# programmer.net
KiCad netlist of a schematic drawn in EAGLE
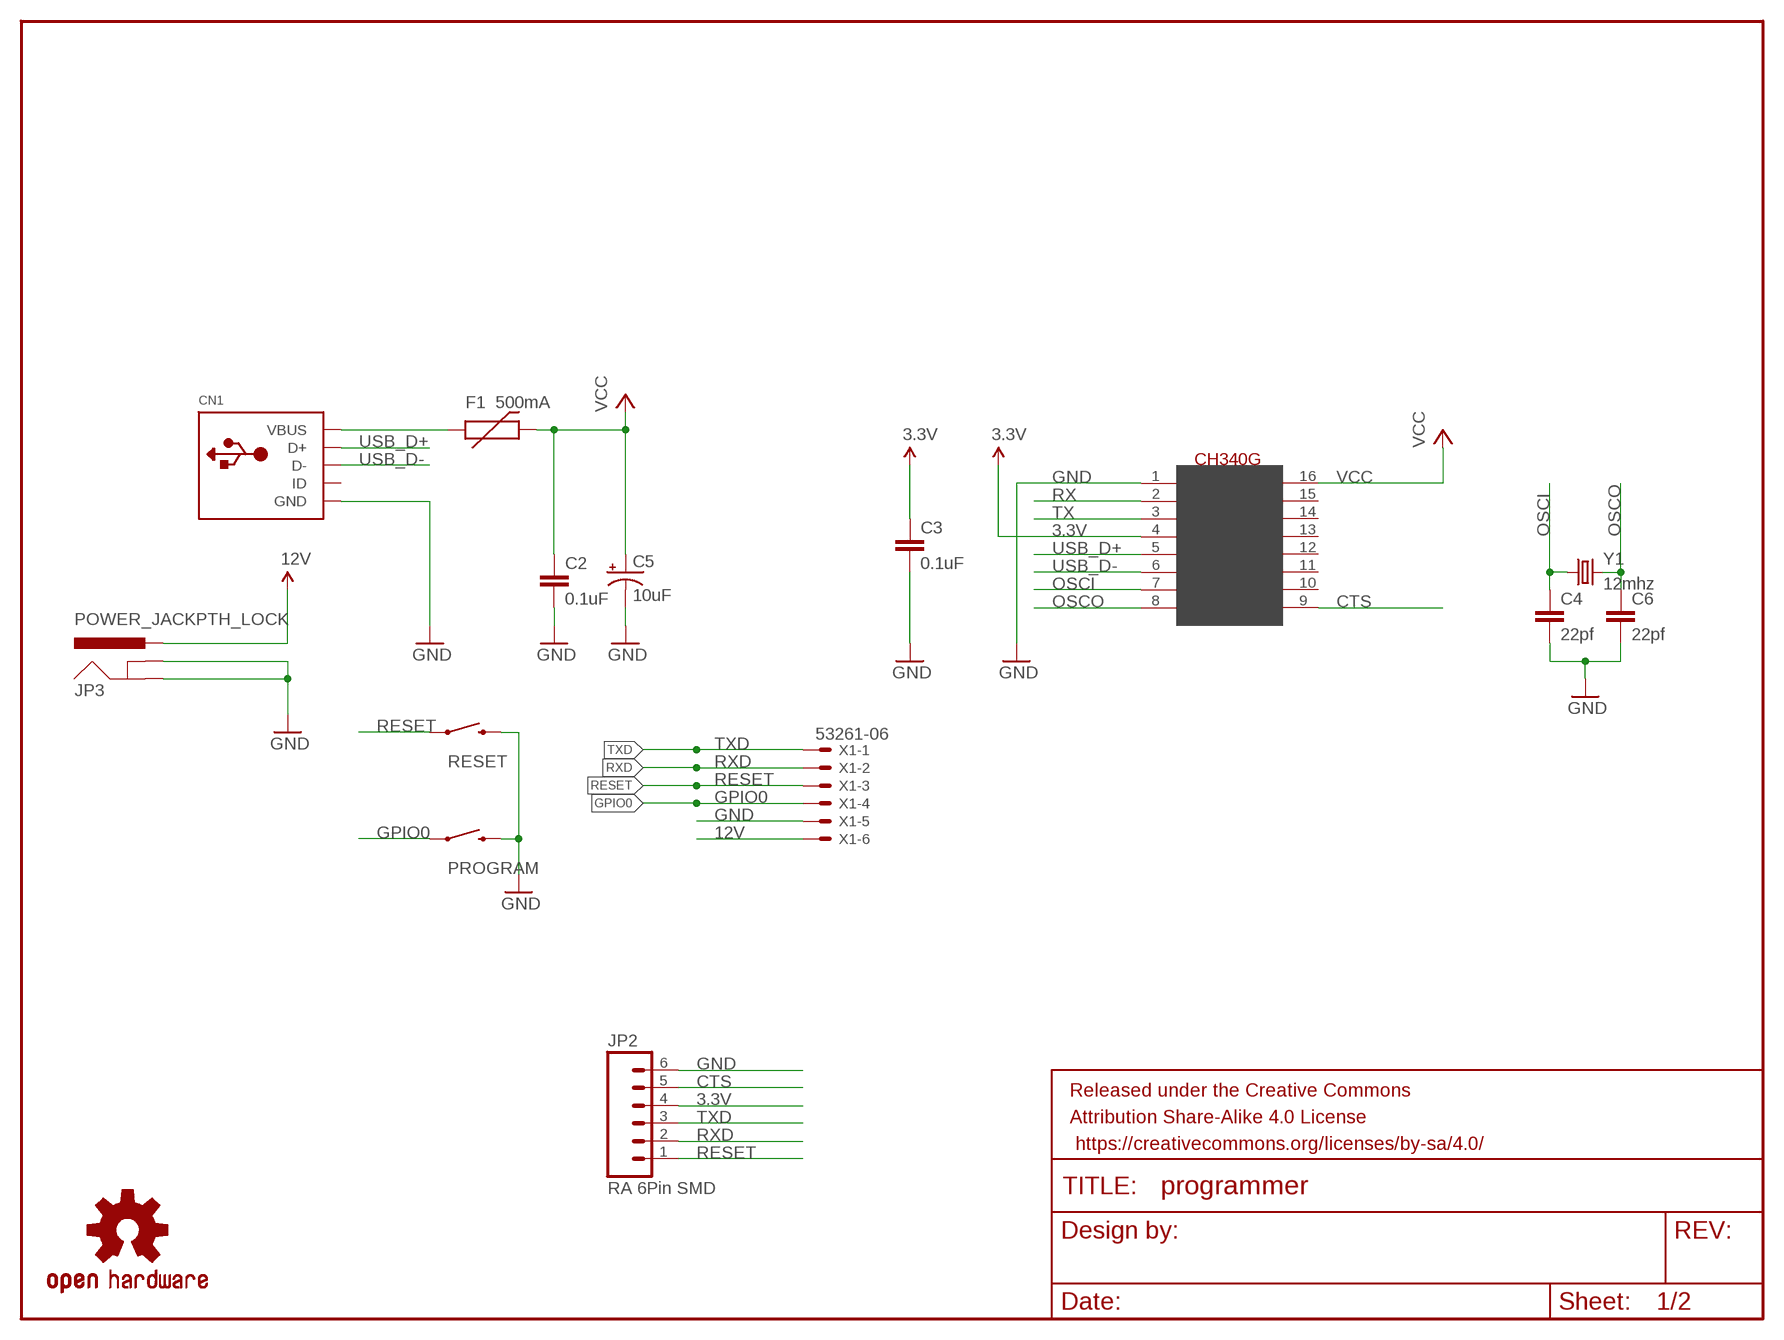
[diagram p0: schematic, sheet 1]

(export (version "E")
  (design (tool "Eeschema 10.0.6"))
  (components
    (comp (ref "C2")
      (value "0.1uF")
      (footprint "eagle-import:1206")
      (libsource (lib "eagle-import") (part "SparkFun-Passives_CAP1206"))
    )
    (comp (ref "C3")
      (value "0.1uF")
      (footprint "eagle-import:C1206K")
      (libsource (lib "eagle-import") (part "C-EUC1206K"))
    )
    (comp (ref "C4")
      (value "22pf")
      (footprint "eagle-import:1206")
      (libsource (lib "eagle-import") (part "CAP1206"))
    )
    (comp (ref "C5")
      (value "10uF")
      (footprint "eagle-import:EIA3216")
      (libsource (lib "eagle-import") (part "10UF-16V-10%(TANT)"))
    )
    (comp (ref "C6")
      (value "22pf")
      (footprint "eagle-import:1206")
      (libsource (lib "eagle-import") (part "CAP1206"))
    )
    (comp (ref "CN1")
      (value "USBMINIB")
      (footprint "eagle-import:USB-MINIB")
      (libsource (lib "eagle-import") (part "USBMINIB"))
    )
    (comp (ref "F1")
      (value "500mA")
      (footprint "eagle-import:PTC-1206")
      (libsource (lib "eagle-import") (part "PTCSMD"))
    )
    (comp (ref "FRAME1")
      (value "FRAME-LETTERNO_PACKAGE")
      (footprint "eagle-import:DUMMY")
      (fields (field (name "DESIGNER") "Nobody"))
      (libsource (lib "eagle-import") (part "FRAME-LETTERNO_PACKAGE"))
    )
    (comp (ref "JP2")
      (value "RA 6Pin SMD")
      (footprint "eagle-import:1X06-SMD")
      (libsource (lib "eagle-import") (part "M06SMD"))
    )
    (comp (ref "JP3")
      (value "POWER_JACKPTH_LOCK")
      (footprint "eagle-import:POWER_JACK_PTH_LOCK")
      (libsource (lib "eagle-import") (part "POWER_JACKPTH_LOCK"))
    )
    (comp (ref "LOGO1")
      (value "OSHW-LOGOS")
      (footprint "eagle-import:OSHW-LOGO-S")
      (libsource (lib "eagle-import") (part "OSHW-LOGOS"))
    )
    (comp (ref "PROGRAM")
      (value "SWITCH-MOMENTARY-2PTH")
      (footprint "eagle-import:TACTILE-PTH")
      (libsource (lib "eagle-import") (part "SWITCH-MOMENTARY-2PTH"))
    )
    (comp (ref "RESET")
      (value "SWITCH-MOMENTARY-2PTH")
      (footprint "eagle-import:TACTILE-PTH")
      (libsource (lib "eagle-import") (part "SWITCH-MOMENTARY-2PTH"))
    )
    (comp (ref "U$1")
      (value "CH340G")
      (footprint "eagle-import:SOIC16")
      (libsource (lib "eagle-import") (part "CH340G"))
    )
    (comp (ref "X1")
      (value "53261-06")
      (footprint "eagle-import:53261-06")
      (libsource (lib "eagle-import") (part "53?-06261"))
    )
    (comp (ref "Y1")
      (value "12mhz")
      (footprint "eagle-import:HC49UP")
      (libsource (lib "eagle-import") (part "CRYSTALSMD"))
    )
  )
  (nets
    (net (code "1") (name "3.3V") (class "Default")
      (node (ref "C3") (pin "1") (pinfunction "1_1") (pintype "passive"))
      (node (ref "JP2") (pin "4") (pinfunction "4_4") (pintype "passive"))
      (node (ref "U$1") (pin "4") (pinfunction "V3_4") (pintype "bidirectional"))
    )
    (net (code "2") (name "12V") (class "Default")
      (node (ref "JP3") (pin "PWR") (pinfunction "PWR_PWR") (pintype "bidirectional"))
      (node (ref "X1") (pin "6") (pinfunction "S_6") (pintype "passive"))
    )
    (net (code "3") (name "CTS") (class "Default")
      (node (ref "JP2") (pin "5") (pinfunction "5_5") (pintype "passive"))
      (node (ref "U$1") (pin "9") (pinfunction "CTS_9") (pintype "bidirectional"))
    )
    (net (code "4") (name "GND") (class "Default")
      (node (ref "C2") (pin "2") (pinfunction "2_2") (pintype "passive"))
      (node (ref "C3") (pin "2") (pinfunction "2_2") (pintype "passive"))
      (node (ref "C4") (pin "2") (pinfunction "2_2") (pintype "passive"))
      (node (ref "C5") (pin "C") (pinfunction "-_C") (pintype "passive"))
      (node (ref "C6") (pin "2") (pinfunction "2_2") (pintype "passive"))
      (node (ref "CN1") (pin "GND") (pinfunction "GND_GND") (pintype "power_in"))
      (node (ref "JP2") (pin "6") (pinfunction "6_6") (pintype "passive"))
      (node (ref "JP3") (pin "GND") (pinfunction "GND_GND") (pintype "bidirectional"))
      (node (ref "JP3") (pin "GNDBREAK") (pinfunction "GNDBREAK_GNDBREAK") (pintype "bidirectional"))
      (node (ref "PROGRAM") (pin "3") (pinfunction "2_3") (pintype "passive"))
      (node (ref "RESET") (pin "3") (pinfunction "2_3") (pintype "passive"))
      (node (ref "U$1") (pin "1") (pinfunction "GND_1") (pintype "bidirectional"))
      (node (ref "X1") (pin "5") (pinfunction "S_5") (pintype "passive"))
    )
    (net (code "5") (name "GPIO0") (class "Default")
      (node (ref "PROGRAM") (pin "1") (pinfunction "1_1") (pintype "passive"))
      (node (ref "X1") (pin "4") (pinfunction "S_4") (pintype "passive"))
    )
    (net (code "6") (name "Net-(CN1-PadVBUS)") (class "Default")
      (node (ref "CN1") (pin "VBUS") (pinfunction "VBUS_VBUS") (pintype "power_in"))
      (node (ref "F1") (pin "1") (pinfunction "1_1") (pintype "bidirectional"))
    )
    (net (code "7") (name "OSCI") (class "Default")
      (node (ref "C4") (pin "1") (pinfunction "1_1") (pintype "passive"))
      (node (ref "U$1") (pin "7") (pinfunction "XI_7") (pintype "bidirectional"))
      (node (ref "Y1") (pin "1") (pinfunction "1_1") (pintype "passive"))
    )
    (net (code "8") (name "OSCO") (class "Default")
      (node (ref "C6") (pin "1") (pinfunction "1_1") (pintype "passive"))
      (node (ref "U$1") (pin "8") (pinfunction "XO_8") (pintype "bidirectional"))
      (node (ref "Y1") (pin "2") (pinfunction "2_2") (pintype "passive"))
    )
    (net (code "9") (name "RESET") (class "Default")
      (node (ref "JP2") (pin "1") (pinfunction "1_1") (pintype "passive"))
      (node (ref "RESET") (pin "1") (pinfunction "1_1") (pintype "passive"))
      (node (ref "X1") (pin "3") (pinfunction "S_3") (pintype "passive"))
    )
    (net (code "10") (name "RX") (class "Default")
      (node (ref "U$1") (pin "2") (pinfunction "TX_2") (pintype "bidirectional"))
    )
    (net (code "11") (name "RXD") (class "Default")
      (node (ref "JP2") (pin "2") (pinfunction "2_2") (pintype "passive"))
      (node (ref "X1") (pin "2") (pinfunction "S_2") (pintype "passive"))
    )
    (net (code "12") (name "TX") (class "Default")
      (node (ref "U$1") (pin "3") (pinfunction "RX_3") (pintype "bidirectional"))
    )
    (net (code "13") (name "TXD") (class "Default")
      (node (ref "JP2") (pin "3") (pinfunction "3_3") (pintype "passive"))
      (node (ref "X1") (pin "1") (pinfunction "S_1") (pintype "passive"))
    )
    (net (code "14") (name "USB_D+") (class "Default")
      (node (ref "CN1") (pin "D+") (pinfunction "D+_D+") (pintype "bidirectional"))
      (node (ref "U$1") (pin "5") (pinfunction "D+_5") (pintype "bidirectional"))
    )
    (net (code "15") (name "USB_D-") (class "Default")
      (node (ref "CN1") (pin "D-") (pinfunction "D-_D-") (pintype "bidirectional"))
      (node (ref "U$1") (pin "6") (pinfunction "D-_6") (pintype "bidirectional"))
    )
    (net (code "16") (name "VCC") (class "Default")
      (node (ref "C2") (pin "1") (pinfunction "1_1") (pintype "passive"))
      (node (ref "C5") (pin "A") (pinfunction "+_A") (pintype "passive"))
      (node (ref "F1") (pin "2") (pinfunction "2_2") (pintype "bidirectional"))
      (node (ref "U$1") (pin "16") (pinfunction "VCC_16") (pintype "bidirectional"))
    )
    (net (code "17") (name "unconnected-(CN1-PadID)") (class "Default")
      (node (ref "CN1") (pin "ID") (pinfunction "ID_ID") (pintype "bidirectional"))
    )
    (net (code "18") (name "unconnected-(U$1-DCD-Pad12)") (class "Default")
      (node (ref "U$1") (pin "12") (pinfunction "DCD_12") (pintype "bidirectional"))
    )
    (net (code "19") (name "unconnected-(U$1-DSR-Pad10)") (class "Default")
      (node (ref "U$1") (pin "10") (pinfunction "DSR_10") (pintype "bidirectional"))
    )
    (net (code "20") (name "unconnected-(U$1-DTR-Pad13)") (class "Default")
      (node (ref "U$1") (pin "13") (pinfunction "DTR_13") (pintype "bidirectional"))
    )
    (net (code "21") (name "unconnected-(U$1-RI-Pad11)") (class "Default")
      (node (ref "U$1") (pin "11") (pinfunction "RI_11") (pintype "bidirectional"))
    )
    (net (code "22") (name "unconnected-(U$1-RS232-Pad15)") (class "Default")
      (node (ref "U$1") (pin "15") (pinfunction "RS232_15") (pintype "bidirectional"))
    )
    (net (code "23") (name "unconnected-(U$1-RTS-Pad14)") (class "Default")
      (node (ref "U$1") (pin "14") (pinfunction "RTS_14") (pintype "bidirectional"))
    )
  )
)
